# GSE_Analog_Remote_BOTTOM_Schematic_v1_Ea.net
KiCad netlist of a schematic drawn in EasyEDA
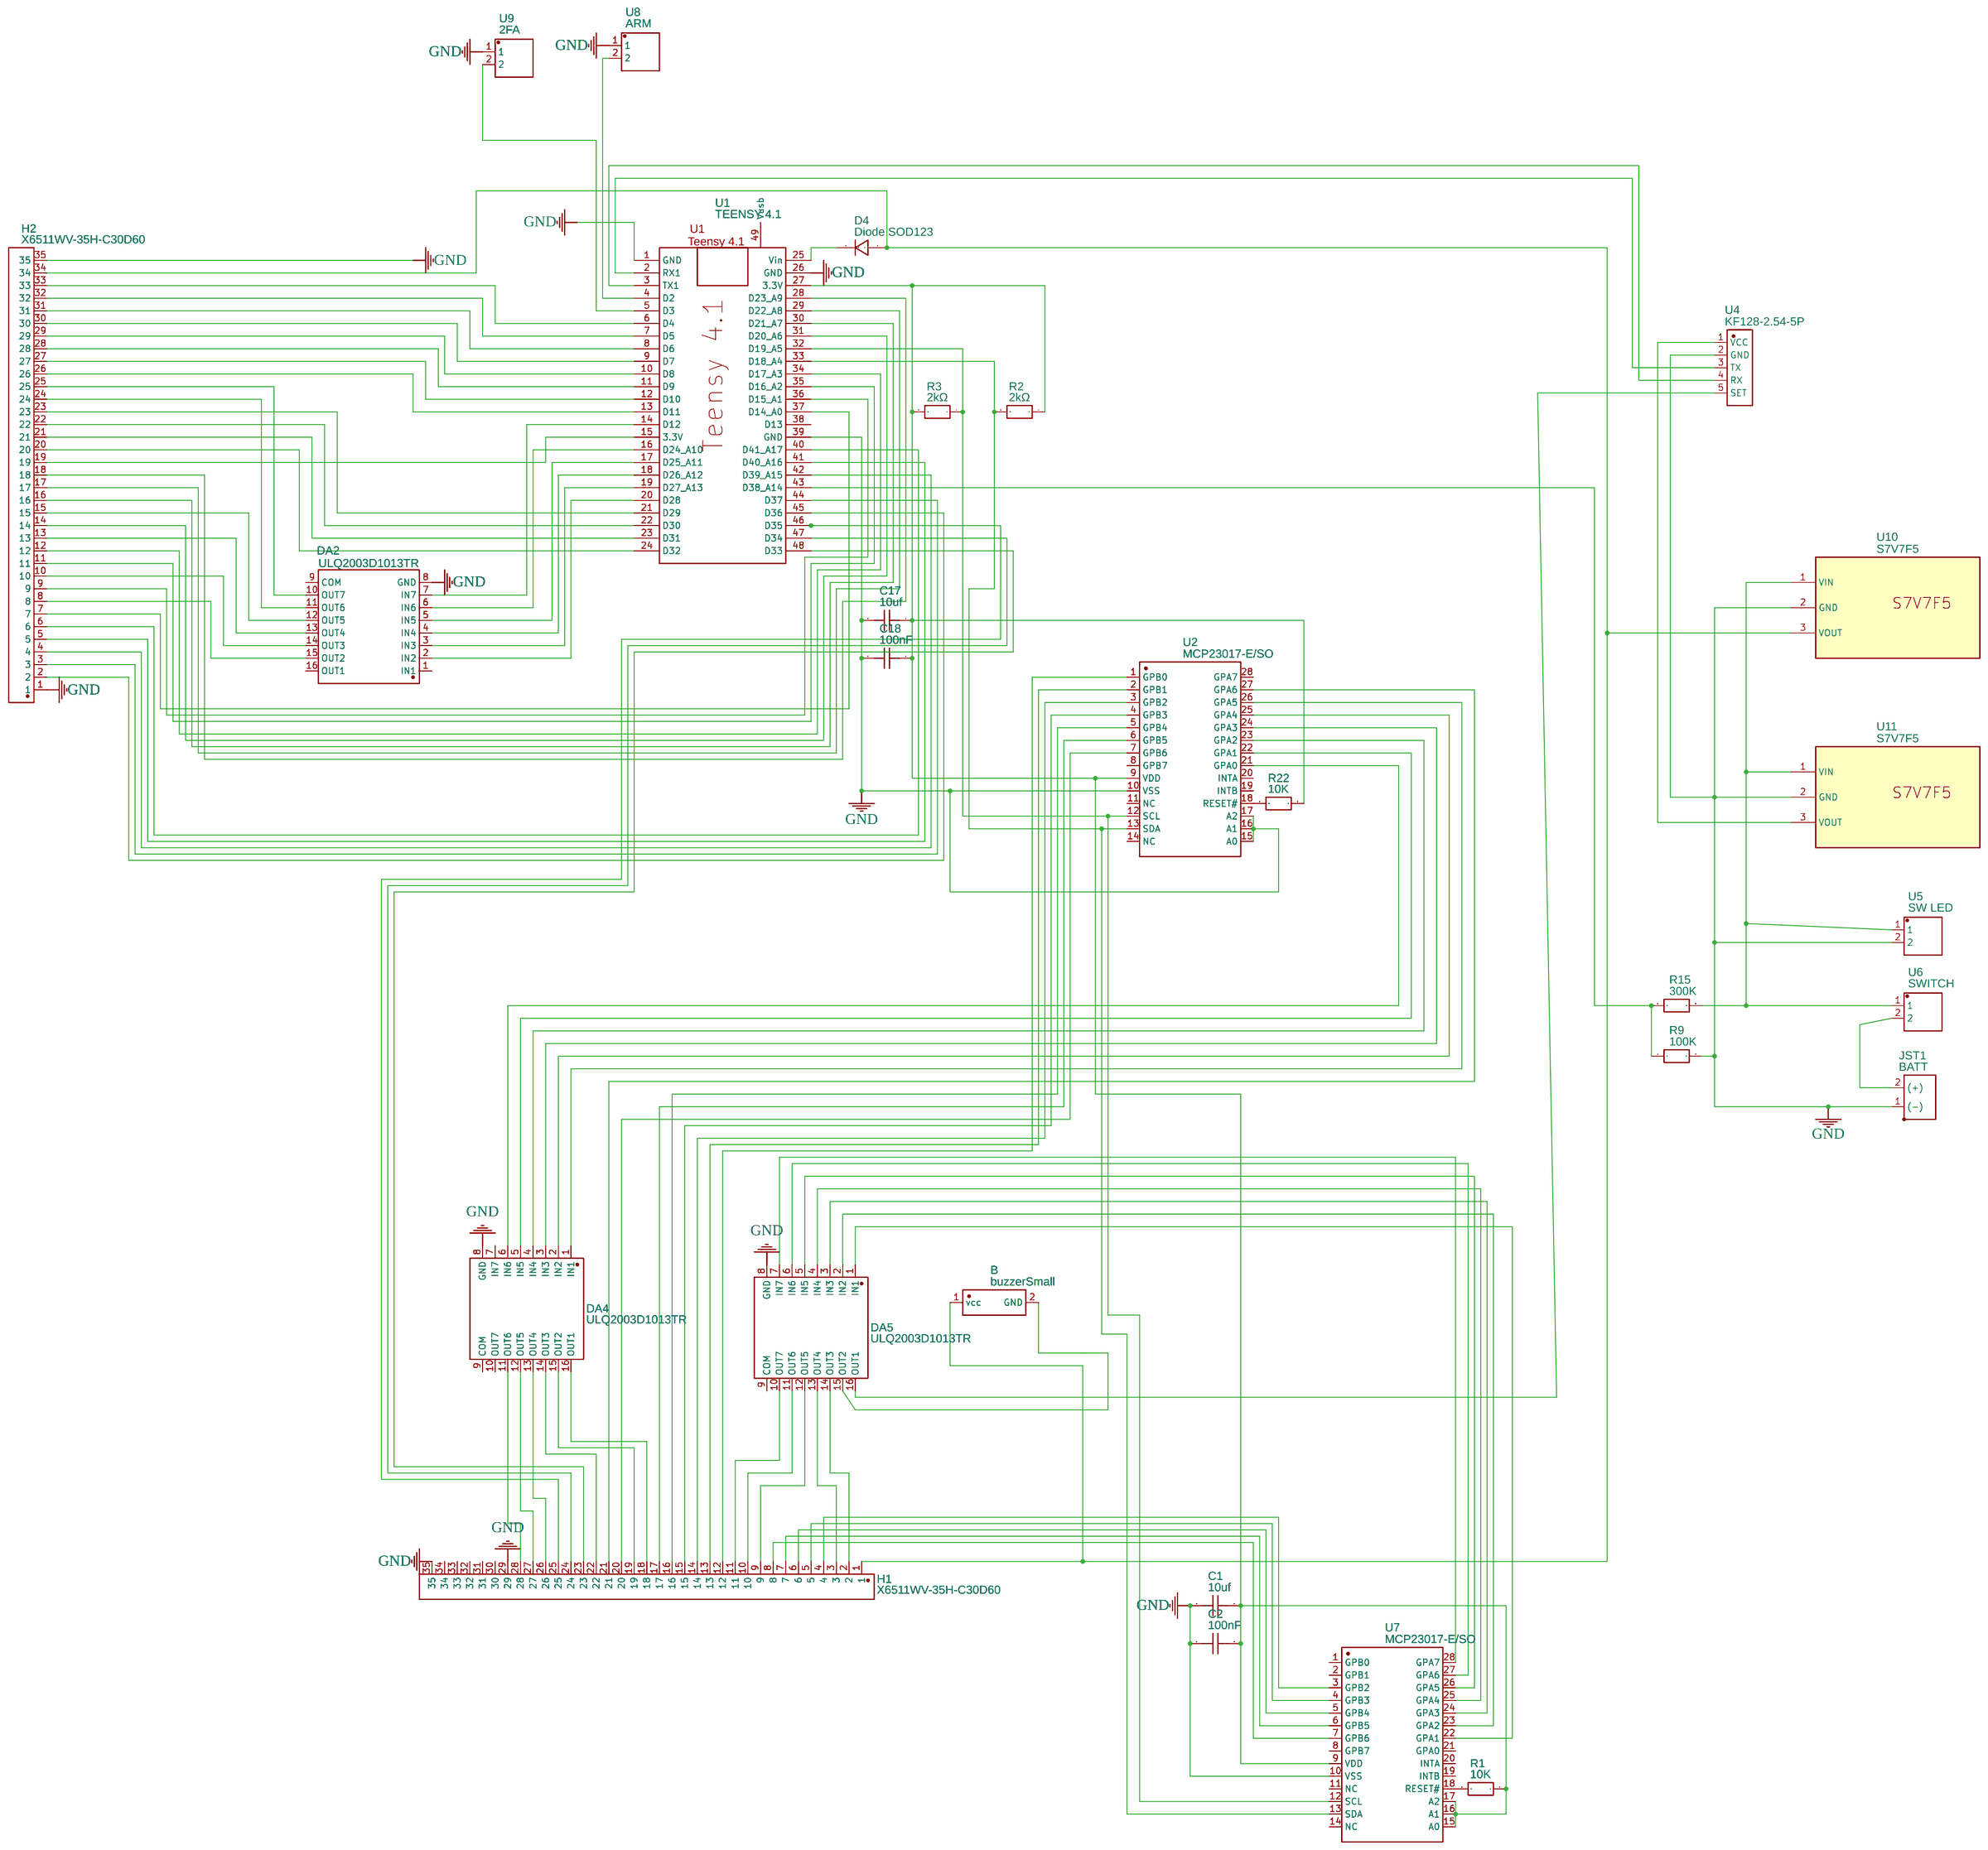
[diagram p0: schematic sheet]

(export (version "E")
  (design (tool "Eeschema 10.0.6"))
  (components
    (comp (ref "B") (value "buzzerSmall") (libsource (lib "") (part "buzzerSmall")))
    (comp (ref "C1")
      (value "10uf")
      (fields (field (name "Manufacturer Part") "CC0402KRX7R6BB104") (field (name "Manufacturer") "YAGEO"))
      (libsource (lib "") (part "CC0402KRX7R6BB104"))
    )
    (comp (ref "C2")
      (value "100nF")
      (fields (field (name "Manufacturer Part") "CC0402KRX7R6BB104") (field (name "Manufacturer") "YAGEO"))
      (libsource (lib "") (part "CC0402KRX7R6BB104"))
    )
    (comp (ref "C17")
      (value "10uf")
      (fields (field (name "Manufacturer Part") "CC0402KRX7R6BB104") (field (name "Manufacturer") "YAGEO"))
      (libsource (lib "") (part "CC0402KRX7R6BB104"))
    )
    (comp (ref "C18")
      (value "100nF")
      (fields (field (name "Manufacturer Part") "CC0402KRX7R6BB104") (field (name "Manufacturer") "YAGEO"))
      (libsource (lib "") (part "CC0402KRX7R6BB104"))
    )
    (comp (ref "D4")
      (value "Diode SOD123")
      (fields
        (field (name "Manufacturer Part") "S15MLW RVG")
        (field (name "Manufacturer") "Taiwan Semiconductor(Taiwan Semicon)")
      )
      (libsource (lib "") (part "S15MLW RVG"))
    )
    (comp (ref "DA2")
      (value "ULQ2003D1013TR")
      (fields (field (name "Manufacturer") "STMicroelectronics"))
      (libsource (lib "") (part "ULQ2003D1013TR_1"))
    )
    (comp (ref "DA4")
      (value "ULQ2003D1013TR")
      (fields (field (name "Manufacturer") "STMicroelectronics"))
      (libsource (lib "") (part "ULQ2003D1013TR"))
    )
    (comp (ref "DA5")
      (value "ULQ2003D1013TR")
      (fields (field (name "Manufacturer") "STMicroelectronics"))
      (libsource (lib "") (part "ULQ2003D1013TR"))
    )
    (comp (ref "H1")
      (value "X6511WV-35H-C30D60")
      (fields (field (name "Manufacturer") "XKB Connectivity(中国星坤)"))
      (libsource (lib "") (part "X6511WV-35H-C30D60_1"))
    )
    (comp (ref "H2")
      (value "X6511WV-35H-C30D60")
      (fields (field (name "Manufacturer") "XKB Connectivity(中国星坤)"))
      (libsource (lib "") (part "X6511WV-35H-C30D60"))
    )
    (comp (ref "JST1") (value "BATT") (libsource (lib "") (part "JST2X")))
    (comp (ref "R1")
      (value "10K")
      (fields (field (name "Manufacturer Part") "ERA6AEB202V") (field (name "Manufacturer") "PANASONIC"))
      (libsource (lib "") (part "ERA6AEB202V"))
    )
    (comp (ref "R2")
      (value "2kΩ")
      (fields (field (name "Manufacturer Part") "ERA6AEB202V") (field (name "Manufacturer") "PANASONIC"))
      (libsource (lib "") (part "ERA6AEB202V"))
    )
    (comp (ref "R3")
      (value "2kΩ")
      (fields (field (name "Manufacturer Part") "ERA6AEB202V") (field (name "Manufacturer") "PANASONIC"))
      (libsource (lib "") (part "ERA6AEB202V"))
    )
    (comp (ref "R9")
      (value "100K")
      (fields (field (name "Manufacturer Part") "ERJP06J221V") (field (name "Manufacturer") "PANASONIC"))
      (libsource (lib "") (part "ERJP06J221V"))
    )
    (comp (ref "R15")
      (value "300K")
      (fields (field (name "Manufacturer Part") "ERJP06J221V") (field (name "Manufacturer") "PANASONIC"))
      (libsource (lib "") (part "ERJP06J221V"))
    )
    (comp (ref "R22")
      (value "10K")
      (fields (field (name "Manufacturer Part") "ERA6AEB202V") (field (name "Manufacturer") "PANASONIC"))
      (libsource (lib "") (part "ERA6AEB202V"))
    )
    (comp (ref "U1") (value "TEENSY 4.1") (libsource (lib "") (part "TEENSY 4.1")))
    (comp (ref "U2")
      (value "MCP23017-E/SO")
      (fields (field (name "Manufacturer") "MICROCHIP(美国微芯)"))
      (libsource (lib "") (part "MCP23017-E/SO"))
    )
    (comp (ref "U4")
      (value "KF128-2.54-5P")
      (fields (field (name "Manufacturer") "KEFA(科发)"))
      (libsource (lib "") (part "KF128-2.54-5P"))
    )
    (comp (ref "U5")
      (value "SW LED")
      (fields (field (name "Manufacturer Part") "S2B-PH-K-S(LF)(SN)") (field (name "Manufacturer") "JST"))
      (libsource (lib "") (part "S2B-PH-K-S(LF)(SN)"))
    )
    (comp (ref "U6")
      (value "SWITCH")
      (fields (field (name "Manufacturer Part") "S2B-PH-K-S(LF)(SN)") (field (name "Manufacturer") "JST"))
      (libsource (lib "") (part "S2B-PH-K-S(LF)(SN)"))
    )
    (comp (ref "U7")
      (value "MCP23017-E/SO")
      (fields (field (name "Manufacturer") "MICROCHIP(美国微芯)"))
      (libsource (lib "") (part "MCP23017-E/SO"))
    )
    (comp (ref "U8")
      (value "ARM")
      (fields (field (name "Manufacturer Part") "S2B-PH-K-S(LF)(SN)") (field (name "Manufacturer") "JST"))
      (libsource (lib "") (part "S2B-PH-K-S(LF)(SN)"))
    )
    (comp (ref "U9")
      (value "2FA")
      (fields (field (name "Manufacturer Part") "S2B-PH-K-S(LF)(SN)") (field (name "Manufacturer") "JST"))
      (libsource (lib "") (part "S2B-PH-K-S(LF)(SN)"))
    )
    (comp (ref "U10") (value "S7V7F5") (libsource (lib "") (part "S7V7F5")))
    (comp (ref "U11") (value "S7V7F5") (libsource (lib "") (part "S7V7F5")))
  )
  (nets
    (net (code "1") (name "GND") (class "Default")
      (node (ref "C1") (pin "2") (pinfunction "2_2") (pintype "unspecified"))
      (node (ref "C17") (pin "2") (pinfunction "2_2") (pintype "unspecified"))
      (node (ref "C18") (pin "2") (pinfunction "2_2") (pintype "unspecified"))
      (node (ref "C2") (pin "2") (pinfunction "2_2") (pintype "unspecified"))
      (node (ref "DA2") (pin "8") (pinfunction "GND_8") (pintype "unspecified"))
      (node (ref "DA4") (pin "8") (pinfunction "GND_8") (pintype "unspecified"))
      (node (ref "DA5") (pin "8") (pinfunction "GND_8") (pintype "unspecified"))
      (node (ref "H1") (pin "29") (pinfunction "29_29") (pintype "unspecified"))
      (node (ref "H1") (pin "35") (pinfunction "35_35") (pintype "unspecified"))
      (node (ref "H2") (pin "1") (pinfunction "1_1") (pintype "unspecified"))
      (node (ref "H2") (pin "35") (pinfunction "35_35") (pintype "unspecified"))
      (node (ref "JST1") (pin "1") (pinfunction "(-)_1") (pintype "unspecified"))
      (node (ref "R9") (pin "2") (pinfunction "2_2") (pintype "unspecified"))
      (node (ref "U1") (pin "1") (pinfunction "GND_1") (pintype "unspecified"))
      (node (ref "U1") (pin "26") (pinfunction "GND_26") (pintype "unspecified"))
      (node (ref "U1") (pin "39") (pinfunction "GND_39") (pintype "unspecified"))
      (node (ref "U10") (pin "2") (pinfunction "GND_2") (pintype "unspecified"))
      (node (ref "U11") (pin "2") (pinfunction "GND_2") (pintype "unspecified"))
      (node (ref "U2") (pin "10") (pinfunction "VSS_10") (pintype "unspecified"))
      (node (ref "U2") (pin "15") (pinfunction "A0_15") (pintype "unspecified"))
      (node (ref "U2") (pin "16") (pinfunction "A1_16") (pintype "unspecified"))
      (node (ref "U2") (pin "17") (pinfunction "A2_17") (pintype "unspecified"))
      (node (ref "U4") (pin "2") (pinfunction "GND_2") (pintype "unspecified"))
      (node (ref "U5") (pin "2") (pinfunction "2_2") (pintype "unspecified"))
      (node (ref "U7") (pin "10") (pinfunction "VSS_10") (pintype "unspecified"))
      (node (ref "U8") (pin "1") (pinfunction "1_1") (pintype "unspecified"))
      (node (ref "U9") (pin "1") (pinfunction "1_1") (pintype "unspecified"))
    )
    (net (code "2") (name "Net-(B-GND)") (class "Default")
      (node (ref "B") (pin "2") (pinfunction "GND_2") (pintype "unspecified"))
      (node (ref "DA5") (pin "15") (pinfunction "OUT2_15") (pintype "unspecified"))
    )
    (net (code "3") (name "Net-(B-vcc)") (class "Default")
      (node (ref "B") (pin "1") (pinfunction "vcc_1") (pintype "unspecified"))
      (node (ref "D4") (pin "2") (pinfunction "2_2") (pintype "unspecified"))
      (node (ref "H1") (pin "1") (pinfunction "1_1") (pintype "unspecified"))
      (node (ref "H2") (pin "34") (pinfunction "34_34") (pintype "unspecified"))
      (node (ref "U10") (pin "3") (pinfunction "VOUT_3") (pintype "unspecified"))
    )
    (net (code "4") (name "Net-(DA2-IN2)") (class "Default")
      (node (ref "DA2") (pin "2") (pinfunction "IN2_2") (pintype "unspecified"))
      (node (ref "U1") (pin "20") (pinfunction "D28_20") (pintype "unspecified"))
    )
    (net (code "5") (name "Net-(DA2-IN3)") (class "Default")
      (node (ref "DA2") (pin "3") (pinfunction "IN3_3") (pintype "unspecified"))
      (node (ref "U1") (pin "19") (pinfunction "D27_A13_19") (pintype "unspecified"))
    )
    (net (code "6") (name "Net-(DA2-IN4)") (class "Default")
      (node (ref "DA2") (pin "4") (pinfunction "IN4_4") (pintype "unspecified"))
      (node (ref "U1") (pin "18") (pinfunction "D26_A12_18") (pintype "unspecified"))
    )
    (net (code "7") (name "Net-(DA2-IN5)") (class "Default")
      (node (ref "DA2") (pin "5") (pinfunction "IN5_5") (pintype "unspecified"))
      (node (ref "U1") (pin "17") (pinfunction "D25_A11_17") (pintype "unspecified"))
    )
    (net (code "8") (name "Net-(DA2-IN6)") (class "Default")
      (node (ref "DA2") (pin "6") (pinfunction "IN6_6") (pintype "unspecified"))
      (node (ref "U1") (pin "16") (pinfunction "D24_A10_16") (pintype "unspecified"))
    )
    (net (code "9") (name "Net-(DA2-IN7)") (class "Default")
      (node (ref "DA2") (pin "7") (pinfunction "IN7_7") (pintype "unspecified"))
      (node (ref "U1") (pin "14") (pinfunction "D12_14") (pintype "unspecified"))
    )
    (net (code "10") (name "Net-(DA2-OUT2)") (class "Default")
      (node (ref "DA2") (pin "15") (pinfunction "OUT2_15") (pintype "unspecified"))
      (node (ref "H2") (pin "8") (pinfunction "8_8") (pintype "unspecified"))
    )
    (net (code "11") (name "Net-(DA2-OUT3)") (class "Default")
      (node (ref "DA2") (pin "14") (pinfunction "OUT3_14") (pintype "unspecified"))
      (node (ref "H2") (pin "10") (pinfunction "10_10") (pintype "unspecified"))
    )
    (net (code "12") (name "Net-(DA2-OUT4)") (class "Default")
      (node (ref "DA2") (pin "13") (pinfunction "OUT4_13") (pintype "unspecified"))
      (node (ref "H2") (pin "13") (pinfunction "13_13") (pintype "unspecified"))
    )
    (net (code "13") (name "Net-(DA2-OUT5)") (class "Default")
      (node (ref "DA2") (pin "12") (pinfunction "OUT5_12") (pintype "unspecified"))
      (node (ref "H2") (pin "15") (pinfunction "15_15") (pintype "unspecified"))
    )
    (net (code "14") (name "Net-(DA2-OUT6)") (class "Default")
      (node (ref "DA2") (pin "11") (pinfunction "OUT6_11") (pintype "unspecified"))
      (node (ref "H2") (pin "24") (pinfunction "24_24") (pintype "unspecified"))
    )
    (net (code "15") (name "Net-(DA2-OUT7)") (class "Default")
      (node (ref "DA2") (pin "10") (pinfunction "OUT7_10") (pintype "unspecified"))
      (node (ref "H2") (pin "25") (pinfunction "25_25") (pintype "unspecified"))
    )
    (net (code "16") (name "Net-(DA4-IN1)") (class "Default")
      (node (ref "DA4") (pin "1") (pinfunction "IN1_1") (pintype "unspecified"))
      (node (ref "U2") (pin "26") (pinfunction "GPA5_26") (pintype "unspecified"))
    )
    (net (code "17") (name "Net-(DA4-IN2)") (class "Default")
      (node (ref "DA4") (pin "2") (pinfunction "IN2_2") (pintype "unspecified"))
      (node (ref "U2") (pin "25") (pinfunction "GPA4_25") (pintype "unspecified"))
    )
    (net (code "18") (name "Net-(DA4-IN3)") (class "Default")
      (node (ref "DA4") (pin "3") (pinfunction "IN3_3") (pintype "unspecified"))
      (node (ref "U2") (pin "24") (pinfunction "GPA3_24") (pintype "unspecified"))
    )
    (net (code "19") (name "Net-(DA4-IN4)") (class "Default")
      (node (ref "DA4") (pin "4") (pinfunction "IN4_4") (pintype "unspecified"))
      (node (ref "U2") (pin "23") (pinfunction "GPA2_23") (pintype "unspecified"))
    )
    (net (code "20") (name "Net-(DA4-IN5)") (class "Default")
      (node (ref "DA4") (pin "5") (pinfunction "IN5_5") (pintype "unspecified"))
      (node (ref "U2") (pin "22") (pinfunction "GPA1_22") (pintype "unspecified"))
    )
    (net (code "21") (name "Net-(DA4-IN6)") (class "Default")
      (node (ref "DA4") (pin "6") (pinfunction "IN6_6") (pintype "unspecified"))
      (node (ref "U2") (pin "21") (pinfunction "GPA0_21") (pintype "unspecified"))
    )
    (net (code "22") (name "Net-(DA4-OUT1)") (class "Default")
      (node (ref "DA4") (pin "16") (pinfunction "OUT1_16") (pintype "unspecified"))
      (node (ref "H1") (pin "18") (pinfunction "18_18") (pintype "unspecified"))
    )
    (net (code "23") (name "Net-(DA4-OUT2)") (class "Default")
      (node (ref "DA4") (pin "15") (pinfunction "OUT2_15") (pintype "unspecified"))
      (node (ref "H1") (pin "19") (pinfunction "19_19") (pintype "unspecified"))
    )
    (net (code "24") (name "Net-(DA4-OUT3)") (class "Default")
      (node (ref "DA4") (pin "14") (pinfunction "OUT3_14") (pintype "unspecified"))
      (node (ref "H1") (pin "22") (pinfunction "22_22") (pintype "unspecified"))
    )
    (net (code "25") (name "Net-(DA4-OUT4)") (class "Default")
      (node (ref "DA4") (pin "13") (pinfunction "OUT4_13") (pintype "unspecified"))
      (node (ref "H1") (pin "26") (pinfunction "26_26") (pintype "unspecified"))
    )
    (net (code "26") (name "Net-(DA4-OUT5)") (class "Default")
      (node (ref "DA4") (pin "12") (pinfunction "OUT5_12") (pintype "unspecified"))
      (node (ref "H1") (pin "27") (pinfunction "27_27") (pintype "unspecified"))
    )
    (net (code "27") (name "Net-(DA4-OUT6)") (class "Default")
      (node (ref "DA4") (pin "11") (pinfunction "OUT6_11") (pintype "unspecified"))
      (node (ref "H1") (pin "28") (pinfunction "28_28") (pintype "unspecified"))
    )
    (net (code "28") (name "Net-(DA5-IN1)") (class "Default")
      (node (ref "DA5") (pin "1") (pinfunction "IN1_1") (pintype "unspecified"))
      (node (ref "U7") (pin "22") (pinfunction "GPA1_22") (pintype "unspecified"))
    )
    (net (code "29") (name "Net-(DA5-IN2)") (class "Default")
      (node (ref "DA5") (pin "2") (pinfunction "IN2_2") (pintype "unspecified"))
      (node (ref "U7") (pin "23") (pinfunction "GPA2_23") (pintype "unspecified"))
    )
    (net (code "30") (name "Net-(DA5-IN3)") (class "Default")
      (node (ref "DA5") (pin "3") (pinfunction "IN3_3") (pintype "unspecified"))
      (node (ref "U7") (pin "24") (pinfunction "GPA3_24") (pintype "unspecified"))
    )
    (net (code "31") (name "Net-(DA5-IN4)") (class "Default")
      (node (ref "DA5") (pin "4") (pinfunction "IN4_4") (pintype "unspecified"))
      (node (ref "U7") (pin "25") (pinfunction "GPA4_25") (pintype "unspecified"))
    )
    (net (code "32") (name "Net-(DA5-IN5)") (class "Default")
      (node (ref "DA5") (pin "5") (pinfunction "IN5_5") (pintype "unspecified"))
      (node (ref "U7") (pin "26") (pinfunction "GPA5_26") (pintype "unspecified"))
    )
    (net (code "33") (name "Net-(DA5-IN6)") (class "Default")
      (node (ref "DA5") (pin "6") (pinfunction "IN6_6") (pintype "unspecified"))
      (node (ref "U7") (pin "27") (pinfunction "GPA6_27") (pintype "unspecified"))
    )
    (net (code "34") (name "Net-(DA5-IN7)") (class "Default")
      (node (ref "DA5") (pin "7") (pinfunction "IN7_7") (pintype "unspecified"))
      (node (ref "U7") (pin "28") (pinfunction "GPA7_28") (pintype "unspecified"))
    )
    (net (code "35") (name "Net-(DA5-OUT1)") (class "Default")
      (node (ref "DA5") (pin "16") (pinfunction "OUT1_16") (pintype "unspecified"))
      (node (ref "U4") (pin "5") (pinfunction "SET_5") (pintype "unspecified"))
    )
    (net (code "36") (name "Net-(DA5-OUT3)") (class "Default")
      (node (ref "DA5") (pin "14") (pinfunction "OUT3_14") (pintype "unspecified"))
      (node (ref "H1") (pin "2") (pinfunction "2_2") (pintype "unspecified"))
    )
    (net (code "37") (name "Net-(DA5-OUT4)") (class "Default")
      (node (ref "DA5") (pin "13") (pinfunction "OUT4_13") (pintype "unspecified"))
      (node (ref "H1") (pin "3") (pinfunction "3_3") (pintype "unspecified"))
    )
    (net (code "38") (name "Net-(DA5-OUT5)") (class "Default")
      (node (ref "DA5") (pin "12") (pinfunction "OUT5_12") (pintype "unspecified"))
      (node (ref "H1") (pin "9") (pinfunction "9_9") (pintype "unspecified"))
    )
    (net (code "39") (name "Net-(DA5-OUT6)") (class "Default")
      (node (ref "DA5") (pin "11") (pinfunction "OUT6_11") (pintype "unspecified"))
      (node (ref "H1") (pin "10") (pinfunction "10_10") (pintype "unspecified"))
    )
    (net (code "40") (name "Net-(DA5-OUT7)") (class "Default")
      (node (ref "DA5") (pin "10") (pinfunction "OUT7_10") (pintype "unspecified"))
      (node (ref "H1") (pin "11") (pinfunction "11_11") (pintype "unspecified"))
    )
    (net (code "41") (name "Net-(H2-Pad19)") (class "Default")
      (node (ref "H2") (pin "19") (pinfunction "19_19") (pintype "unspecified"))
      (node (ref "U1") (pin "15") (pinfunction "3.3V_15") (pintype "unspecified"))
    )
    (net (code "42") (name "Net-(JST1-(+))") (class "Default")
      (node (ref "JST1") (pin "2") (pinfunction "(+)_2") (pintype "unspecified"))
      (node (ref "U6") (pin "2") (pinfunction "2_2") (pintype "unspecified"))
    )
    (net (code "43") (name "Net-(U1-D2)") (class "Default")
      (node (ref "U1") (pin "4") (pinfunction "D2_4") (pintype "unspecified"))
      (node (ref "U8") (pin "2") (pinfunction "2_2") (pintype "unspecified"))
    )
    (net (code "44") (name "Net-(U1-D3)") (class "Default")
      (node (ref "U1") (pin "5") (pinfunction "D3_5") (pintype "unspecified"))
      (node (ref "U9") (pin "2") (pinfunction "2_2") (pintype "unspecified"))
    )
    (net (code "45") (name "Net-(U1-D4)") (class "Default")
      (node (ref "H2") (pin "33") (pinfunction "33_33") (pintype "unspecified"))
      (node (ref "U1") (pin "6") (pinfunction "D4_6") (pintype "unspecified"))
    )
    (net (code "46") (name "Net-(U1-D5)") (class "Default")
      (node (ref "H2") (pin "32") (pinfunction "32_32") (pintype "unspecified"))
      (node (ref "U1") (pin "7") (pinfunction "D5_7") (pintype "unspecified"))
    )
    (net (code "47") (name "Net-(U1-D6)") (class "Default")
      (node (ref "H2") (pin "31") (pinfunction "31_31") (pintype "unspecified"))
      (node (ref "U1") (pin "8") (pinfunction "D6_8") (pintype "unspecified"))
    )
    (net (code "48") (name "Net-(U1-D7)") (class "Default")
      (node (ref "H2") (pin "30") (pinfunction "30_30") (pintype "unspecified"))
      (node (ref "U1") (pin "9") (pinfunction "D7_9") (pintype "unspecified"))
    )
    (net (code "49") (name "Net-(U1-D8)") (class "Default")
      (node (ref "H2") (pin "29") (pinfunction "29_29") (pintype "unspecified"))
      (node (ref "U1") (pin "10") (pinfunction "D8_10") (pintype "unspecified"))
    )
    (net (code "50") (name "Net-(U1-D9)") (class "Default")
      (node (ref "H2") (pin "28") (pinfunction "28_28") (pintype "unspecified"))
      (node (ref "U1") (pin "11") (pinfunction "D9_11") (pintype "unspecified"))
    )
    (net (code "51") (name "Net-(U1-D10)") (class "Default")
      (node (ref "H2") (pin "27") (pinfunction "27_27") (pintype "unspecified"))
      (node (ref "U1") (pin "12") (pinfunction "D10_12") (pintype "unspecified"))
    )
    (net (code "52") (name "Net-(U1-D11)") (class "Default")
      (node (ref "H2") (pin "26") (pinfunction "26_26") (pintype "unspecified"))
      (node (ref "U1") (pin "13") (pinfunction "D11_13") (pintype "unspecified"))
    )
    (net (code "53") (name "Net-(U1-D14_A0)") (class "Default")
      (node (ref "H2") (pin "7") (pinfunction "7_7") (pintype "unspecified"))
      (node (ref "U1") (pin "37") (pinfunction "D14_A0_37") (pintype "unspecified"))
    )
    (net (code "54") (name "Net-(U1-D15_A1)") (class "Default")
      (node (ref "H2") (pin "9") (pinfunction "9_9") (pintype "unspecified"))
      (node (ref "U1") (pin "36") (pinfunction "D15_A1_36") (pintype "unspecified"))
    )
    (net (code "55") (name "Net-(U1-D16_A2)") (class "Default")
      (node (ref "H2") (pin "11") (pinfunction "11_11") (pintype "unspecified"))
      (node (ref "U1") (pin "35") (pinfunction "D16_A2_35") (pintype "unspecified"))
    )
    (net (code "56") (name "Net-(U1-D17_A3)") (class "Default")
      (node (ref "H2") (pin "12") (pinfunction "12_12") (pintype "unspecified"))
      (node (ref "U1") (pin "34") (pinfunction "D17_A3_34") (pintype "unspecified"))
    )
    (net (code "57") (name "Net-(U1-D18_A4)") (class "Default")
      (node (ref "R2") (pin "2") (pinfunction "2_2") (pintype "unspecified"))
      (node (ref "U1") (pin "33") (pinfunction "D18_A4_33") (pintype "unspecified"))
      (node (ref "U2") (pin "13") (pinfunction "SDA_13") (pintype "unspecified"))
      (node (ref "U7") (pin "13") (pinfunction "SDA_13") (pintype "unspecified"))
    )
    (net (code "58") (name "Net-(U1-D19_A5)") (class "Default")
      (node (ref "R3") (pin "1") (pinfunction "1_1") (pintype "unspecified"))
      (node (ref "U1") (pin "32") (pinfunction "D19_A5_32") (pintype "unspecified"))
      (node (ref "U2") (pin "12") (pinfunction "SCL_12") (pintype "unspecified"))
      (node (ref "U7") (pin "12") (pinfunction "SCL_12") (pintype "unspecified"))
    )
    (net (code "59") (name "Net-(U1-D20_A6)") (class "Default")
      (node (ref "H2") (pin "14") (pinfunction "14_14") (pintype "unspecified"))
      (node (ref "U1") (pin "31") (pinfunction "D20_A6_31") (pintype "unspecified"))
    )
    (net (code "60") (name "Net-(U1-D21_A7)") (class "Default")
      (node (ref "H2") (pin "16") (pinfunction "16_16") (pintype "unspecified"))
      (node (ref "U1") (pin "30") (pinfunction "D21_A7_30") (pintype "unspecified"))
    )
    (net (code "61") (name "Net-(U1-D22_A8)") (class "Default")
      (node (ref "H2") (pin "17") (pinfunction "17_17") (pintype "unspecified"))
      (node (ref "U1") (pin "29") (pinfunction "D22_A8_29") (pintype "unspecified"))
    )
    (net (code "62") (name "Net-(U1-D23_A9)") (class "Default")
      (node (ref "H2") (pin "18") (pinfunction "18_18") (pintype "unspecified"))
      (node (ref "U1") (pin "28") (pinfunction "D23_A9_28") (pintype "unspecified"))
    )
    (net (code "63") (name "Net-(U1-D29)") (class "Default")
      (node (ref "H2") (pin "23") (pinfunction "23_23") (pintype "unspecified"))
      (node (ref "U1") (pin "21") (pinfunction "D29_21") (pintype "unspecified"))
    )
    (net (code "64") (name "Net-(U1-D30)") (class "Default")
      (node (ref "H2") (pin "22") (pinfunction "22_22") (pintype "unspecified"))
      (node (ref "U1") (pin "22") (pinfunction "D30_22") (pintype "unspecified"))
    )
    (net (code "65") (name "Net-(U1-D31)") (class "Default")
      (node (ref "H2") (pin "21") (pinfunction "21_21") (pintype "unspecified"))
      (node (ref "U1") (pin "23") (pinfunction "D31_23") (pintype "unspecified"))
    )
    (net (code "66") (name "Net-(U1-D32)") (class "Default")
      (node (ref "H2") (pin "20") (pinfunction "20_20") (pintype "unspecified"))
      (node (ref "U1") (pin "24") (pinfunction "D32_24") (pintype "unspecified"))
    )
    (net (code "67") (name "Net-(U1-D33)") (class "Default")
      (node (ref "H1") (pin "23") (pinfunction "23_23") (pintype "unspecified"))
      (node (ref "U1") (pin "48") (pinfunction "D33_48") (pintype "unspecified"))
    )
    (net (code "68") (name "Net-(U1-D34)") (class "Default")
      (node (ref "H1") (pin "24") (pinfunction "24_24") (pintype "unspecified"))
      (node (ref "U1") (pin "47") (pinfunction "D34_47") (pintype "unspecified"))
    )
    (net (code "69") (name "Net-(U1-D35)") (class "Default")
      (node (ref "H1") (pin "25") (pinfunction "25_25") (pintype "unspecified"))
      (node (ref "U1") (pin "46") (pinfunction "D35_46") (pintype "unspecified"))
    )
    (net (code "70") (name "Net-(U1-D36)") (class "Default")
      (node (ref "H2") (pin "2") (pinfunction "2_2") (pintype "unspecified"))
      (node (ref "U1") (pin "45") (pinfunction "D36_45") (pintype "unspecified"))
    )
    (net (code "71") (name "Net-(U1-D37)") (class "Default")
      (node (ref "H2") (pin "3") (pinfunction "3_3") (pintype "unspecified"))
      (node (ref "U1") (pin "44") (pinfunction "D37_44") (pintype "unspecified"))
    )
    (net (code "72") (name "Net-(U1-D38_A14)") (class "Default")
      (node (ref "R15") (pin "1") (pinfunction "1_1") (pintype "unspecified"))
      (node (ref "R9") (pin "1") (pinfunction "1_1") (pintype "unspecified"))
      (node (ref "U1") (pin "43") (pinfunction "D38_A14_43") (pintype "unspecified"))
    )
    (net (code "73") (name "Net-(U1-D39_A15)") (class "Default")
      (node (ref "H2") (pin "4") (pinfunction "4_4") (pintype "unspecified"))
      (node (ref "U1") (pin "42") (pinfunction "D39_A15_42") (pintype "unspecified"))
    )
    (net (code "74") (name "Net-(U1-D40_A16)") (class "Default")
      (node (ref "H2") (pin "5") (pinfunction "5_5") (pintype "unspecified"))
      (node (ref "U1") (pin "41") (pinfunction "D40_A16_41") (pintype "unspecified"))
    )
    (net (code "75") (name "Net-(U1-D41_A17)") (class "Default")
      (node (ref "H2") (pin "6") (pinfunction "6_6") (pintype "unspecified"))
      (node (ref "U1") (pin "40") (pinfunction "D41_A17_40") (pintype "unspecified"))
    )
    (net (code "76") (name "Net-(U1-RX1)") (class "Default")
      (node (ref "U1") (pin "2") (pinfunction "RX1_2") (pintype "unspecified"))
      (node (ref "U4") (pin "3") (pinfunction "TX_3") (pintype "unspecified"))
    )
    (net (code "77") (name "Net-(U1-TX1)") (class "Default")
      (node (ref "U1") (pin "3") (pinfunction "TX1_3") (pintype "unspecified"))
      (node (ref "U4") (pin "4") (pinfunction "RX_4") (pintype "unspecified"))
    )
    (net (code "78") (name "Net-(U1-Vin)") (class "Default")
      (node (ref "D4") (pin "1") (pinfunction "1_1") (pintype "unspecified"))
      (node (ref "U1") (pin "25") (pinfunction "Vin_25") (pintype "unspecified"))
    )
    (net (code "79") (name "Net-(U2-GPA6)") (class "Default")
      (node (ref "H1") (pin "21") (pinfunction "21_21") (pintype "unspecified"))
      (node (ref "U2") (pin "27") (pinfunction "GPA6_27") (pintype "unspecified"))
    )
    (net (code "80") (name "Net-(U2-GPB0)") (class "Default")
      (node (ref "H1") (pin "12") (pinfunction "12_12") (pintype "unspecified"))
      (node (ref "U2") (pin "1") (pinfunction "GPB0_1") (pintype "unspecified"))
    )
    (net (code "81") (name "Net-(U2-GPB1)") (class "Default")
      (node (ref "H1") (pin "13") (pinfunction "13_13") (pintype "unspecified"))
      (node (ref "U2") (pin "2") (pinfunction "GPB1_2") (pintype "unspecified"))
    )
    (net (code "82") (name "Net-(U2-GPB2)") (class "Default")
      (node (ref "H1") (pin "14") (pinfunction "14_14") (pintype "unspecified"))
      (node (ref "U2") (pin "3") (pinfunction "GPB2_3") (pintype "unspecified"))
    )
    (net (code "83") (name "Net-(U2-GPB3)") (class "Default")
      (node (ref "H1") (pin "15") (pinfunction "15_15") (pintype "unspecified"))
      (node (ref "U2") (pin "4") (pinfunction "GPB3_4") (pintype "unspecified"))
    )
    (net (code "84") (name "Net-(U2-GPB4)") (class "Default")
      (node (ref "H1") (pin "16") (pinfunction "16_16") (pintype "unspecified"))
      (node (ref "U2") (pin "5") (pinfunction "GPB4_5") (pintype "unspecified"))
    )
    (net (code "85") (name "Net-(U2-GPB5)") (class "Default")
      (node (ref "H1") (pin "17") (pinfunction "17_17") (pintype "unspecified"))
      (node (ref "U2") (pin "6") (pinfunction "GPB5_6") (pintype "unspecified"))
    )
    (net (code "86") (name "Net-(U2-GPB6)") (class "Default")
      (node (ref "H1") (pin "20") (pinfunction "20_20") (pintype "unspecified"))
      (node (ref "U2") (pin "7") (pinfunction "GPB6_7") (pintype "unspecified"))
    )
    (net (code "87") (name "Net-(U2-RESET#)") (class "Default")
      (node (ref "R22") (pin "2") (pinfunction "2_2") (pintype "unspecified"))
      (node (ref "U2") (pin "18") (pinfunction "RESET#_18") (pintype "unspecified"))
    )
    (net (code "88") (name "Net-(U2-VDD)") (class "Default")
      (node (ref "C1") (pin "1") (pinfunction "1_1") (pintype "unspecified"))
      (node (ref "C17") (pin "1") (pinfunction "1_1") (pintype "unspecified"))
      (node (ref "C18") (pin "1") (pinfunction "1_1") (pintype "unspecified"))
      (node (ref "C2") (pin "1") (pinfunction "1_1") (pintype "unspecified"))
      (node (ref "R1") (pin "1") (pinfunction "1_1") (pintype "unspecified"))
      (node (ref "R2") (pin "1") (pinfunction "1_1") (pintype "unspecified"))
      (node (ref "R22") (pin "1") (pinfunction "1_1") (pintype "unspecified"))
      (node (ref "R3") (pin "2") (pinfunction "2_2") (pintype "unspecified"))
      (node (ref "U1") (pin "27") (pinfunction "3.3V_27") (pintype "unspecified"))
      (node (ref "U2") (pin "9") (pinfunction "VDD_9") (pintype "unspecified"))
      (node (ref "U7") (pin "15") (pinfunction "A0_15") (pintype "unspecified"))
      (node (ref "U7") (pin "16") (pinfunction "A1_16") (pintype "unspecified"))
      (node (ref "U7") (pin "17") (pinfunction "A2_17") (pintype "unspecified"))
      (node (ref "U7") (pin "9") (pinfunction "VDD_9") (pintype "unspecified"))
    )
    (net (code "89") (name "Net-(U7-GPB2)") (class "Default")
      (node (ref "H1") (pin "4") (pinfunction "4_4") (pintype "unspecified"))
      (node (ref "U7") (pin "3") (pinfunction "GPB2_3") (pintype "unspecified"))
    )
    (net (code "90") (name "Net-(U7-GPB3)") (class "Default")
      (node (ref "H1") (pin "5") (pinfunction "5_5") (pintype "unspecified"))
      (node (ref "U7") (pin "4") (pinfunction "GPB3_4") (pintype "unspecified"))
    )
    (net (code "91") (name "Net-(U7-GPB4)") (class "Default")
      (node (ref "H1") (pin "6") (pinfunction "6_6") (pintype "unspecified"))
      (node (ref "U7") (pin "5") (pinfunction "GPB4_5") (pintype "unspecified"))
    )
    (net (code "92") (name "Net-(U7-GPB5)") (class "Default")
      (node (ref "H1") (pin "7") (pinfunction "7_7") (pintype "unspecified"))
      (node (ref "U7") (pin "6") (pinfunction "GPB5_6") (pintype "unspecified"))
    )
    (net (code "93") (name "Net-(U7-GPB6)") (class "Default")
      (node (ref "H1") (pin "8") (pinfunction "8_8") (pintype "unspecified"))
      (node (ref "U7") (pin "7") (pinfunction "GPB6_7") (pintype "unspecified"))
    )
    (net (code "94") (name "Net-(U7-RESET#)") (class "Default")
      (node (ref "R1") (pin "2") (pinfunction "2_2") (pintype "unspecified"))
      (node (ref "U7") (pin "18") (pinfunction "RESET#_18") (pintype "unspecified"))
    )
    (net (code "95") (name "Net-(U10-VIN)") (class "Default")
      (node (ref "R15") (pin "2") (pinfunction "2_2") (pintype "unspecified"))
      (node (ref "U10") (pin "1") (pinfunction "VIN_1") (pintype "unspecified"))
      (node (ref "U11") (pin "1") (pinfunction "VIN_1") (pintype "unspecified"))
      (node (ref "U5") (pin "1") (pinfunction "1_1") (pintype "unspecified"))
      (node (ref "U6") (pin "1") (pinfunction "1_1") (pintype "unspecified"))
    )
    (net (code "96") (name "Net-(U11-VOUT)") (class "Default")
      (node (ref "U11") (pin "3") (pinfunction "VOUT_3") (pintype "unspecified"))
      (node (ref "U4") (pin "1") (pinfunction "VCC_1") (pintype "unspecified"))
    )
    (net (code "97") (name "unconnected-(DA2-COM-Pad9)") (class "Default")
      (node (ref "DA2") (pin "9") (pinfunction "COM_9") (pintype "unspecified"))
    )
    (net (code "98") (name "unconnected-(DA2-IN1-Pad1)") (class "Default")
      (node (ref "DA2") (pin "1") (pinfunction "IN1_1") (pintype "unspecified"))
    )
    (net (code "99") (name "unconnected-(DA2-OUT1-Pad16)") (class "Default")
      (node (ref "DA2") (pin "16") (pinfunction "OUT1_16") (pintype "unspecified"))
    )
    (net (code "100") (name "unconnected-(DA4-COM-Pad9)") (class "Default")
      (node (ref "DA4") (pin "9") (pinfunction "COM_9") (pintype "unspecified"))
    )
    (net (code "101") (name "unconnected-(DA4-IN7-Pad7)") (class "Default")
      (node (ref "DA4") (pin "7") (pinfunction "IN7_7") (pintype "unspecified"))
    )
    (net (code "102") (name "unconnected-(DA4-OUT7-Pad10)") (class "Default")
      (node (ref "DA4") (pin "10") (pinfunction "OUT7_10") (pintype "unspecified"))
    )
    (net (code "103") (name "unconnected-(DA5-COM-Pad9)") (class "Default")
      (node (ref "DA5") (pin "9") (pinfunction "COM_9") (pintype "unspecified"))
    )
    (net (code "104") (name "unconnected-(H1-Pad30)") (class "Default")
      (node (ref "H1") (pin "30") (pinfunction "30_30") (pintype "unspecified"))
    )
    (net (code "105") (name "unconnected-(H1-Pad31)") (class "Default")
      (node (ref "H1") (pin "31") (pinfunction "31_31") (pintype "unspecified"))
    )
    (net (code "106") (name "unconnected-(H1-Pad32)") (class "Default")
      (node (ref "H1") (pin "32") (pinfunction "32_32") (pintype "unspecified"))
    )
    (net (code "107") (name "unconnected-(H1-Pad33)") (class "Default")
      (node (ref "H1") (pin "33") (pinfunction "33_33") (pintype "unspecified"))
    )
    (net (code "108") (name "unconnected-(H1-Pad34)") (class "Default")
      (node (ref "H1") (pin "34") (pinfunction "34_34") (pintype "unspecified"))
    )
    (net (code "109") (name "unconnected-(U1-D13-Pad38)") (class "Default")
      (node (ref "U1") (pin "38") (pinfunction "D13_38") (pintype "unspecified"))
    )
    (net (code "110") (name "unconnected-(U1-Vusb-Pad49)") (class "Default")
      (node (ref "U1") (pin "49") (pinfunction "Vusb_49") (pintype "unspecified"))
    )
    (net (code "111") (name "unconnected-(U2-GPA7-Pad28)") (class "Default")
      (node (ref "U2") (pin "28") (pinfunction "GPA7_28") (pintype "unspecified"))
    )
    (net (code "112") (name "unconnected-(U2-GPB7-Pad8)") (class "Default")
      (node (ref "U2") (pin "8") (pinfunction "GPB7_8") (pintype "unspecified"))
    )
    (net (code "113") (name "unconnected-(U2-INTA-Pad20)") (class "Default")
      (node (ref "U2") (pin "20") (pinfunction "INTA_20") (pintype "unspecified"))
    )
    (net (code "114") (name "unconnected-(U2-INTB-Pad19)") (class "Default")
      (node (ref "U2") (pin "19") (pinfunction "INTB_19") (pintype "unspecified"))
    )
    (net (code "115") (name "unconnected-(U2-NC-Pad11)") (class "Default")
      (node (ref "U2") (pin "11") (pinfunction "NC_11") (pintype "unspecified"))
    )
    (net (code "116") (name "unconnected-(U2-NC-Pad14)") (class "Default")
      (node (ref "U2") (pin "14") (pinfunction "NC_14") (pintype "unspecified"))
    )
    (net (code "117") (name "unconnected-(U7-GPA0-Pad21)") (class "Default")
      (node (ref "U7") (pin "21") (pinfunction "GPA0_21") (pintype "unspecified"))
    )
    (net (code "118") (name "unconnected-(U7-GPB0-Pad1)") (class "Default")
      (node (ref "U7") (pin "1") (pinfunction "GPB0_1") (pintype "unspecified"))
    )
    (net (code "119") (name "unconnected-(U7-GPB1-Pad2)") (class "Default")
      (node (ref "U7") (pin "2") (pinfunction "GPB1_2") (pintype "unspecified"))
    )
    (net (code "120") (name "unconnected-(U7-GPB7-Pad8)") (class "Default")
      (node (ref "U7") (pin "8") (pinfunction "GPB7_8") (pintype "unspecified"))
    )
    (net (code "121") (name "unconnected-(U7-INTA-Pad20)") (class "Default")
      (node (ref "U7") (pin "20") (pinfunction "INTA_20") (pintype "unspecified"))
    )
    (net (code "122") (name "unconnected-(U7-INTB-Pad19)") (class "Default")
      (node (ref "U7") (pin "19") (pinfunction "INTB_19") (pintype "unspecified"))
    )
    (net (code "123") (name "unconnected-(U7-NC-Pad11)") (class "Default")
      (node (ref "U7") (pin "11") (pinfunction "NC_11") (pintype "unspecified"))
    )
    (net (code "124") (name "unconnected-(U7-NC-Pad14)") (class "Default")
      (node (ref "U7") (pin "14") (pinfunction "NC_14") (pintype "unspecified"))
    )
  )
)
